# ad.net
KiCad netlist of a schematic drawn in Altium Designer
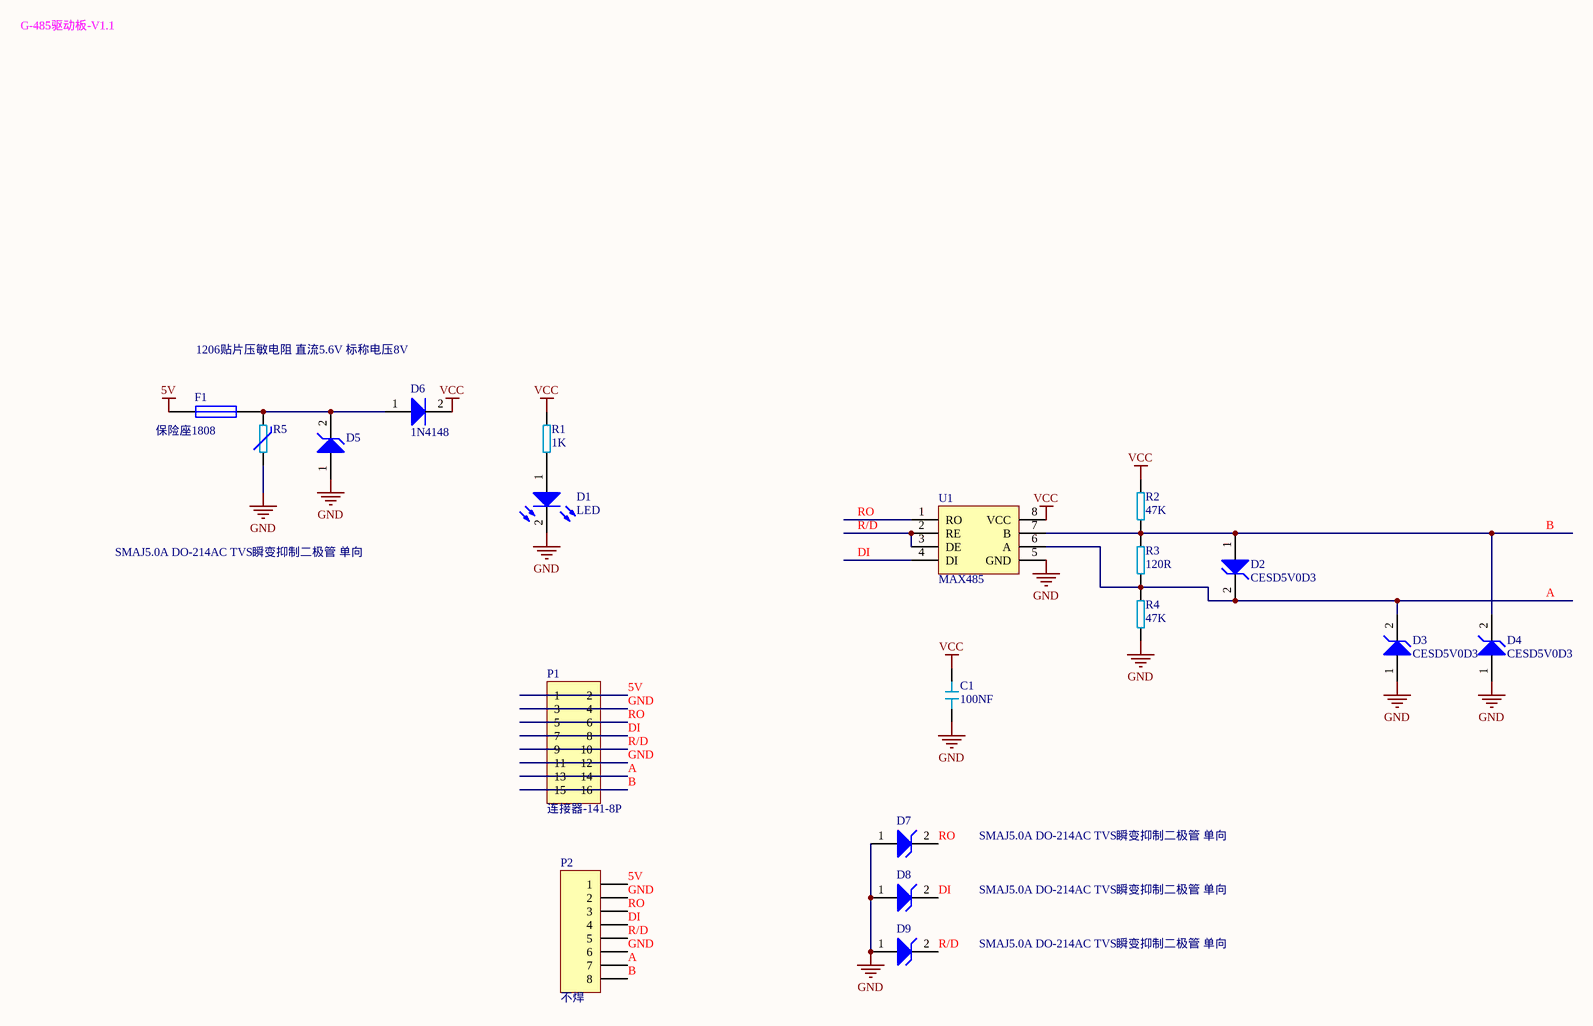
[diagram p0: ad.SchDoc]

(export (version "E")
  (design (tool "Eeschema 10.0.6"))
  (components
    (comp (ref "C1")
      (value "100NF")
      (footprint "C0603")
      (description "贴片电容")
      (libsource (lib "base") (part "C0603"))
    )
    (comp (ref "D1")
      (value "LED")
      (footprint "LED0603")
      (description "LED0603")
      (fields (field (name "PUBLISHER") "Altium Limited"))
      (libsource (lib "base") (part "LED0603"))
    )
    (comp (ref "D2")
      (value "CESD5V0D3")
      (footprint "SOD323")
      (description "稳压管")
      (fields (field (name "PUBLISHER") "Altium Limited"))
      (libsource (lib "base") (part "TVS-SMA"))
    )
    (comp (ref "D3")
      (value "CESD5V0D3")
      (footprint "SOD323")
      (description "稳压管")
      (fields (field (name "PUBLISHER") "Altium Limited"))
      (libsource (lib "base") (part "TVS-SMA"))
    )
    (comp (ref "D4")
      (value "CESD5V0D3")
      (footprint "SOD323")
      (description "稳压管")
      (fields (field (name "PUBLISHER") "Altium Limited"))
      (libsource (lib "base") (part "TVS-SMA"))
    )
    (comp (ref "D5")
      (value "SMAJ5.0A DO-214AC TVS瞬变抑制二极管 单向")
      (footprint "SMA")
      (description "稳压管")
      (fields (field (name "PUBLISHER") "Altium Limited"))
      (libsource (lib "base") (part "TVS-SMA"))
    )
    (comp (ref "D6")
      (value "1N4148")
      (footprint "SOD123")
      (description "二极管")
      (fields (field (name "PUBLISHER") "Altium Limited"))
      (libsource (lib "base") (part "DD"))
    )
    (comp (ref "D7")
      (value "SMAJ5.0A DO-214AC TVS瞬变抑制二极管 单向")
      (footprint "SMA")
      (description "稳压管")
      (fields (field (name "PUBLISHER") "Altium Limited"))
      (libsource (lib "base") (part "TVS-SMA"))
    )
    (comp (ref "D8")
      (value "SMAJ5.0A DO-214AC TVS瞬变抑制二极管 单向")
      (footprint "SMA")
      (description "稳压管")
      (fields (field (name "PUBLISHER") "Altium Limited"))
      (libsource (lib "base") (part "TVS-SMA"))
    )
    (comp (ref "D9")
      (value "SMAJ5.0A DO-214AC TVS瞬变抑制二极管 单向")
      (footprint "SMA")
      (description "稳压管")
      (fields (field (name "PUBLISHER") "Altium Limited"))
      (libsource (lib "base") (part "TVS-SMA"))
    )
    (comp (ref "F1")
      (value "保险座1808")
      (footprint "F1808-ZUO")
      (description "自恢复保险")
      (fields (field (name "PUBLISHER") "Altium Limited"))
      (libsource (lib "base") (part "Fuse0805"))
    )
    (comp (ref "P1")
      (value "连接器-141-8P")
      (footprint "141V-8P")
      (description "连接器")
      (fields (field (name "PUBLISHER") "Altium Limited"))
      (libsource (lib "base") (part "DIC16"))
    )
    (comp (ref "P2")
      (value "不焊")
      (footprint "SIP8")
      (description "连接器")
      (fields (field (name "PUBLISHER") "Altium Limited"))
      (libsource (lib "base") (part "SIP8"))
    )
    (comp (ref "R1")
      (value "1K")
      (footprint "R0603")
      (description "贴片电阻")
      (libsource (lib "base") (part "R-0603"))
    )
    (comp (ref "R2")
      (value "47K")
      (footprint "R0603")
      (description "贴片电阻")
      (libsource (lib "base") (part "R-0603"))
    )
    (comp (ref "R3")
      (value "120R")
      (footprint "R0603")
      (description "贴片电阻")
      (libsource (lib "base") (part "R-0603"))
    )
    (comp (ref "R4")
      (value "47K")
      (footprint "R0603")
      (description "贴片电阻")
      (libsource (lib "base") (part "R-0603"))
    )
    (comp (ref "R5")
      (value "1206贴片压敏电阻 直流5.6V 标称电压8V")
      (footprint "R1206")
      (description "压敏电阻")
      (libsource (lib "base") (part "RV"))
    )
    (comp (ref "U1") (value "MAX485") (footprint "SO8") (libsource (lib "Chip") (part "MAX485")))
  )
  (nets
    (net (code "1") (name "/A") (class "Default")
      (node (ref "D2") (pin "2") (pinfunction "2_2") (pintype "passive"))
      (node (ref "D3") (pin "2") (pinfunction "2_2") (pintype "passive"))
      (node (ref "P1") (pin "13") (pinfunction "13_13") (pintype "passive"))
      (node (ref "P1") (pin "14") (pinfunction "14_14") (pintype "passive"))
      (node (ref "P2") (pin "7") (pinfunction "7_7") (pintype "passive"))
      (node (ref "R3") (pin "1") (pinfunction "1_1") (pintype "passive"))
      (node (ref "R4") (pin "2") (pinfunction "2_2") (pintype "passive"))
      (node (ref "U1") (pin "6") (pinfunction "A_6") (pintype "passive"))
    )
    (net (code "2") (name "/B") (class "Default")
      (node (ref "D2") (pin "1") (pinfunction "1_1") (pintype "passive"))
      (node (ref "D4") (pin "2") (pinfunction "2_2") (pintype "passive"))
      (node (ref "P1") (pin "15") (pinfunction "15_15") (pintype "passive"))
      (node (ref "P1") (pin "16") (pinfunction "16_16") (pintype "passive"))
      (node (ref "P2") (pin "8") (pinfunction "8_8") (pintype "passive"))
      (node (ref "R2") (pin "1") (pinfunction "1_1") (pintype "passive"))
      (node (ref "R3") (pin "2") (pinfunction "2_2") (pintype "passive"))
      (node (ref "U1") (pin "7") (pinfunction "B_7") (pintype "passive"))
    )
    (net (code "3") (name "/DI") (class "Default")
      (node (ref "D8") (pin "2") (pinfunction "2_2") (pintype "passive"))
      (node (ref "P1") (pin "7") (pinfunction "7_7") (pintype "passive"))
      (node (ref "P1") (pin "8") (pinfunction "8_8") (pintype "passive"))
      (node (ref "P2") (pin "4") (pinfunction "4_4") (pintype "passive"))
      (node (ref "U1") (pin "4") (pinfunction "DI_4") (pintype "passive"))
    )
    (net (code "5") (name "/RO") (class "Default")
      (node (ref "D7") (pin "2") (pinfunction "2_2") (pintype "passive"))
      (node (ref "P1") (pin "5") (pinfunction "5_5") (pintype "passive"))
      (node (ref "P1") (pin "6") (pinfunction "6_6") (pintype "passive"))
      (node (ref "P2") (pin "3") (pinfunction "3_3") (pintype "passive"))
      (node (ref "U1") (pin "1") (pinfunction "RO_1") (pintype "passive"))
    )
    (net (code "6") (name "/R{slash}D") (class "Default")
      (node (ref "D9") (pin "2") (pinfunction "2_2") (pintype "passive"))
      (node (ref "P1") (pin "10") (pinfunction "10_10") (pintype "passive"))
      (node (ref "P1") (pin "9") (pinfunction "9_9") (pintype "passive"))
      (node (ref "P2") (pin "5") (pinfunction "5_5") (pintype "passive"))
      (node (ref "U1") (pin "2") (pinfunction "RE_2") (pintype "passive"))
      (node (ref "U1") (pin "3") (pinfunction "DE_3") (pintype "passive"))
    )
    (net (code "7") (name "5V") (class "Default")
      (node (ref "F1") (pin "1") (pinfunction "1_1") (pintype "passive"))
      (node (ref "P1") (pin "1") (pinfunction "1_1") (pintype "passive"))
      (node (ref "P1") (pin "2") (pinfunction "2_2") (pintype "passive"))
      (node (ref "P2") (pin "1") (pinfunction "1_1") (pintype "passive"))
    )
    (net (code "8") (name "GND") (class "Default")
      (node (ref "C1") (pin "1") (pinfunction "1_1") (pintype "passive"))
      (node (ref "D1") (pin "2") (pinfunction "K_2") (pintype "passive"))
      (node (ref "D3") (pin "1") (pinfunction "1_1") (pintype "passive"))
      (node (ref "D4") (pin "1") (pinfunction "1_1") (pintype "passive"))
      (node (ref "D5") (pin "1") (pinfunction "1_1") (pintype "passive"))
      (node (ref "D7") (pin "1") (pinfunction "1_1") (pintype "passive"))
      (node (ref "D8") (pin "1") (pinfunction "1_1") (pintype "passive"))
      (node (ref "D9") (pin "1") (pinfunction "1_1") (pintype "passive"))
      (node (ref "P1") (pin "11") (pinfunction "11_11") (pintype "passive"))
      (node (ref "P1") (pin "12") (pinfunction "12_12") (pintype "passive"))
      (node (ref "P1") (pin "3") (pinfunction "3_3") (pintype "passive"))
      (node (ref "P1") (pin "4") (pinfunction "4_4") (pintype "passive"))
      (node (ref "P2") (pin "2") (pinfunction "2_2") (pintype "passive"))
      (node (ref "P2") (pin "6") (pinfunction "6_6") (pintype "passive"))
      (node (ref "R4") (pin "1") (pinfunction "1_1") (pintype "passive"))
      (node (ref "R5") (pin "1") (pinfunction "1_1") (pintype "passive"))
      (node (ref "U1") (pin "5") (pinfunction "GND_5") (pintype "passive"))
    )
    (net (code "9") (name "Net-(D1-A)") (class "Default")
      (node (ref "D1") (pin "1") (pinfunction "A_1") (pintype "passive"))
      (node (ref "R1") (pin "1") (pinfunction "1_1") (pintype "passive"))
    )
    (net (code "10") (name "Net-(D6-A)") (class "Default")
      (node (ref "D5") (pin "2") (pinfunction "2_2") (pintype "passive"))
      (node (ref "D6") (pin "1") (pinfunction "A_1") (pintype "passive"))
      (node (ref "F1") (pin "2") (pinfunction "2_2") (pintype "passive"))
      (node (ref "R5") (pin "2") (pinfunction "2_2") (pintype "passive"))
    )
    (net (code "11") (name "VCC") (class "Default")
      (node (ref "C1") (pin "2") (pinfunction "2_2") (pintype "passive"))
      (node (ref "D6") (pin "2") (pinfunction "K_2") (pintype "passive"))
      (node (ref "R1") (pin "2") (pinfunction "2_2") (pintype "passive"))
      (node (ref "R2") (pin "2") (pinfunction "2_2") (pintype "passive"))
      (node (ref "U1") (pin "8") (pinfunction "VCC_8") (pintype "passive"))
    )
  )
)
